# 1591XXA-RS485_to_Neopixel_with_RJ45.net
KiCad netlist of a schematic drawn in EAGLE
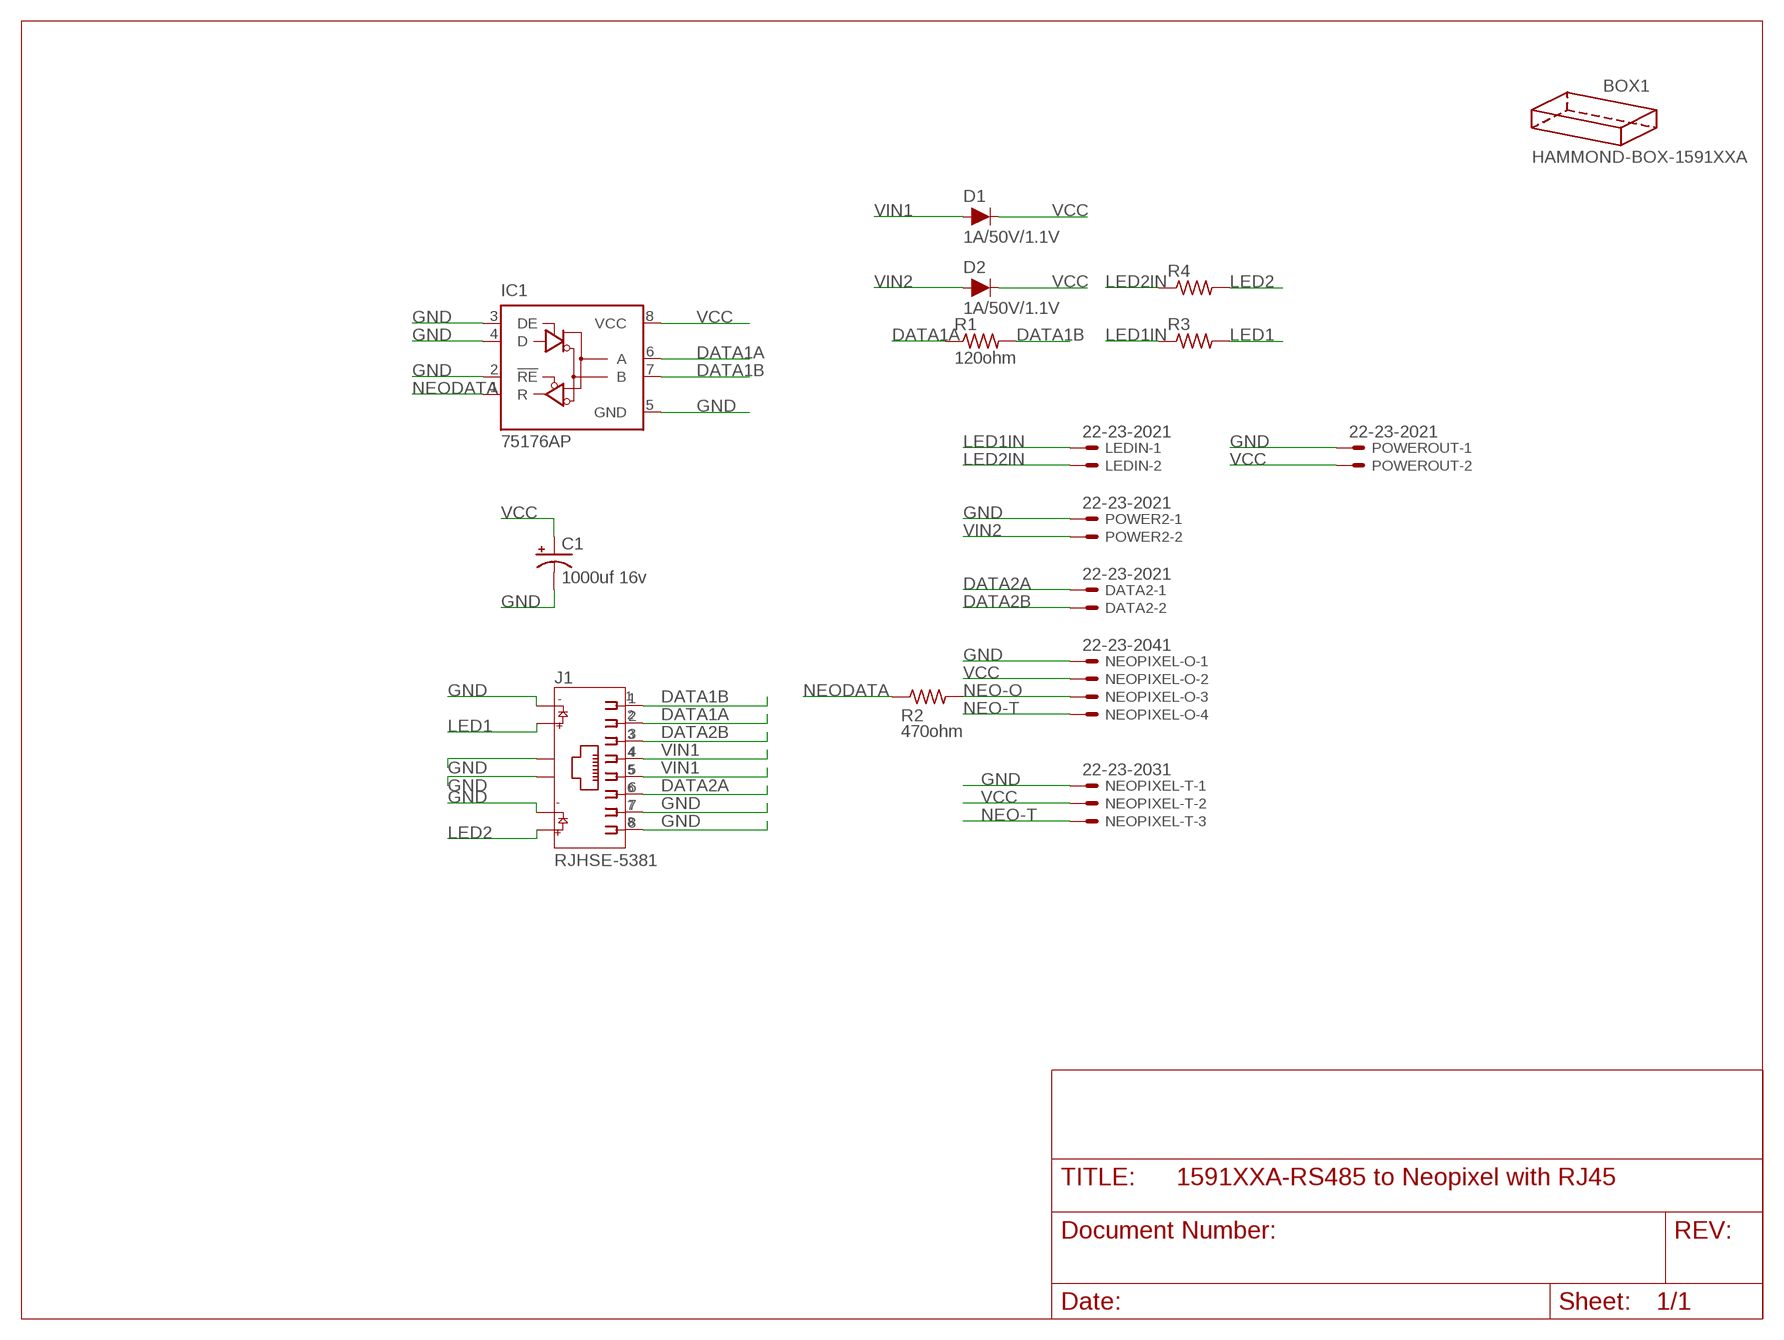
[diagram p0: schematic, sheet 1]

(export (version "E")
  (design (tool "Eeschema 10.0.6"))
  (components
    (comp (ref "BOX1")
      (value "HAMMOND-BOX-1591XXA")
      (footprint "eagle-import:1591XXA")
      (libsource (lib "eagle-import") (part "HAMMOND-BOX-1591XXA"))
    )
    (comp (ref "C1")
      (value "1000uf 16v")
      (footprint "eagle-import:CPOL-RADIAL-5MM-10MM")
      (libsource (lib "eagle-import") (part "1000UF-RADIAL-5MM-25V-20%"))
    )
    (comp (ref "D1")
      (value "1A/50V/1.1V")
      (footprint "eagle-import:DIODE-1N4001")
      (libsource (lib "eagle-import") (part "DIODE-PTH"))
    )
    (comp (ref "D2")
      (value "1A/50V/1.1V")
      (footprint "eagle-import:DIODE-1N4001")
      (libsource (lib "eagle-import") (part "DIODE-PTH"))
    )
    (comp (ref "DATA2")
      (value "22-23-2021")
      (footprint "eagle-import:22-23-2021")
      (fields (field (name "MF") "MOLEX"))
      (libsource (lib "eagle-import") (part "22-23-2021"))
    )
    (comp (ref "IC1")
      (value "75176AP")
      (footprint "eagle-import:DIL08")
      (libsource (lib "eagle-import") (part "75176AP"))
    )
    (comp (ref "J1")
      (value "RJHSE-5381")
      (footprint "eagle-import:AMPHENOL_RJHSE-5381")
      (fields (field (name "MF") "Amphenol ICC"))
      (libsource (lib "eagle-import") (part "RJHSE-5381"))
    )
    (comp (ref "LEDIN")
      (value "22-23-2021")
      (footprint "eagle-import:22-23-2021")
      (fields (field (name "MF") "MOLEX"))
      (libsource (lib "eagle-import") (part "22-23-2021"))
    )
    (comp (ref "NEOPIXEL-O")
      (value "22-23-2041")
      (footprint "eagle-import:22-23-2041")
      (fields (field (name "MF") "MOLEX"))
      (libsource (lib "eagle-import") (part "22-23-2041"))
    )
    (comp (ref "NEOPIXEL-T")
      (value "22-23-2031")
      (footprint "eagle-import:22-23-2031")
      (fields (field (name "MF") "MOLEX"))
      (libsource (lib "eagle-import") (part "22-23-2031"))
    )
    (comp (ref "POWER2")
      (value "22-23-2021")
      (footprint "eagle-import:22-23-2021")
      (fields (field (name "MF") "MOLEX"))
      (libsource (lib "eagle-import") (part "22-23-2021"))
    )
    (comp (ref "POWEROUT")
      (value "22-23-2021")
      (footprint "eagle-import:22-23-2021")
      (fields (field (name "MF") "MOLEX"))
      (libsource (lib "eagle-import") (part "22-23-2021"))
    )
    (comp (ref "R1")
      (value "120ohm")
      (footprint "eagle-import:0207_10")
      (libsource (lib "eagle-import") (part "R-US_0207/10"))
    )
    (comp (ref "R2")
      (value "470ohm")
      (footprint "eagle-import:0207_10")
      (libsource (lib "eagle-import") (part "R-US_0207/10"))
    )
    (comp (ref "R3")
      (value "R-US_0207/10")
      (footprint "eagle-import:0207_10")
      (libsource (lib "eagle-import") (part "R-US_0207/10"))
    )
    (comp (ref "R4")
      (value "R-US_0207/10")
      (footprint "eagle-import:0207_10")
      (libsource (lib "eagle-import") (part "R-US_0207/10"))
    )
  )
  (nets
    (net (code "1") (name "/DATA1A") (class "Default")
      (node (ref "IC1") (pin "6") (pinfunction "A_6") (pintype "output"))
      (node (ref "J1") (pin "2") (pinfunction "2_2") (pintype "passive"))
      (node (ref "R1") (pin "1") (pinfunction "1_1") (pintype "passive"))
    )
    (net (code "2") (name "/DATA1B") (class "Default")
      (node (ref "IC1") (pin "7") (pinfunction "B_7") (pintype "output"))
      (node (ref "J1") (pin "1") (pinfunction "1_1") (pintype "passive"))
      (node (ref "R1") (pin "2") (pinfunction "2_2") (pintype "passive"))
    )
    (net (code "3") (name "/DATA2A") (class "Default")
      (node (ref "DATA2") (pin "1") (pinfunction "S_1") (pintype "passive"))
      (node (ref "J1") (pin "6") (pinfunction "6_6") (pintype "passive"))
    )
    (net (code "4") (name "/DATA2B") (class "Default")
      (node (ref "DATA2") (pin "2") (pinfunction "S_2") (pintype "passive"))
      (node (ref "J1") (pin "3") (pinfunction "3_3") (pintype "passive"))
    )
    (net (code "5") (name "/GND") (class "Default")
      (node (ref "C1") (pin "-") (pinfunction "-_-") (pintype "passive"))
      (node (ref "IC1") (pin "2") (pinfunction "~{RE}_2") (pintype "input"))
      (node (ref "IC1") (pin "3") (pinfunction "DE_3") (pintype "input"))
      (node (ref "IC1") (pin "4") (pinfunction "D_4") (pintype "input"))
      (node (ref "IC1") (pin "5") (pinfunction "GND_5") (pintype "power_in"))
      (node (ref "J1") (pin "11") (pinfunction "11_11") (pintype "passive"))
      (node (ref "J1") (pin "7") (pinfunction "7_7") (pintype "passive"))
      (node (ref "J1") (pin "8") (pinfunction "8_8") (pintype "passive"))
      (node (ref "J1") (pin "9") (pinfunction "9_9") (pintype "passive"))
      (node (ref "J1") (pin "S1") (pinfunction "S1_S1") (pintype "passive"))
      (node (ref "J1") (pin "S2") (pinfunction "S2_S2") (pintype "passive"))
      (node (ref "NEOPIXEL-O") (pin "1") (pinfunction "S_1") (pintype "passive"))
      (node (ref "NEOPIXEL-T") (pin "1") (pinfunction "S_1") (pintype "passive"))
      (node (ref "POWER2") (pin "1") (pinfunction "S_1") (pintype "passive"))
      (node (ref "POWEROUT") (pin "1") (pinfunction "S_1") (pintype "passive"))
    )
    (net (code "6") (name "/LED1") (class "Default")
      (node (ref "J1") (pin "10") (pinfunction "10_10") (pintype "passive"))
      (node (ref "R3") (pin "2") (pinfunction "2_2") (pintype "passive"))
    )
    (net (code "7") (name "/LED1IN") (class "Default")
      (node (ref "LEDIN") (pin "1") (pinfunction "S_1") (pintype "passive"))
      (node (ref "R3") (pin "1") (pinfunction "1_1") (pintype "passive"))
    )
    (net (code "8") (name "/LED2") (class "Default")
      (node (ref "J1") (pin "12") (pinfunction "12_12") (pintype "passive"))
      (node (ref "R4") (pin "2") (pinfunction "2_2") (pintype "passive"))
    )
    (net (code "9") (name "/LED2IN") (class "Default")
      (node (ref "LEDIN") (pin "2") (pinfunction "S_2") (pintype "passive"))
      (node (ref "R4") (pin "1") (pinfunction "1_1") (pintype "passive"))
    )
    (net (code "10") (name "/NEO-O") (class "Default")
      (node (ref "NEOPIXEL-O") (pin "3") (pinfunction "S_3") (pintype "passive"))
      (node (ref "R2") (pin "2") (pinfunction "2_2") (pintype "passive"))
    )
    (net (code "11") (name "/NEO-T") (class "Default")
      (node (ref "NEOPIXEL-O") (pin "4") (pinfunction "S_4") (pintype "passive"))
      (node (ref "NEOPIXEL-T") (pin "3") (pinfunction "S_3") (pintype "passive"))
    )
    (net (code "12") (name "/NEODATA") (class "Default")
      (node (ref "IC1") (pin "1") (pinfunction "R_1") (pintype "input"))
      (node (ref "R2") (pin "1") (pinfunction "1_1") (pintype "passive"))
    )
    (net (code "13") (name "/VCC") (class "Default")
      (node (ref "C1") (pin "+") (pinfunction "+_+") (pintype "passive"))
      (node (ref "D1") (pin "C") (pinfunction "C_C") (pintype "passive"))
      (node (ref "D2") (pin "C") (pinfunction "C_C") (pintype "passive"))
      (node (ref "IC1") (pin "8") (pinfunction "VCC_8") (pintype "power_in"))
      (node (ref "NEOPIXEL-O") (pin "2") (pinfunction "S_2") (pintype "passive"))
      (node (ref "NEOPIXEL-T") (pin "2") (pinfunction "S_2") (pintype "passive"))
      (node (ref "POWEROUT") (pin "2") (pinfunction "S_2") (pintype "passive"))
    )
    (net (code "14") (name "/VIN1") (class "Default")
      (node (ref "D1") (pin "A") (pinfunction "A_A") (pintype "passive"))
      (node (ref "J1") (pin "4") (pinfunction "4_4") (pintype "passive"))
      (node (ref "J1") (pin "5") (pinfunction "5_5") (pintype "passive"))
    )
    (net (code "15") (name "/VIN2") (class "Default")
      (node (ref "D2") (pin "A") (pinfunction "A_A") (pintype "passive"))
      (node (ref "POWER2") (pin "2") (pinfunction "S_2") (pintype "passive"))
    )
  )
)
